# DI.net
KiCad netlist of a schematic drawn in Altium Designer
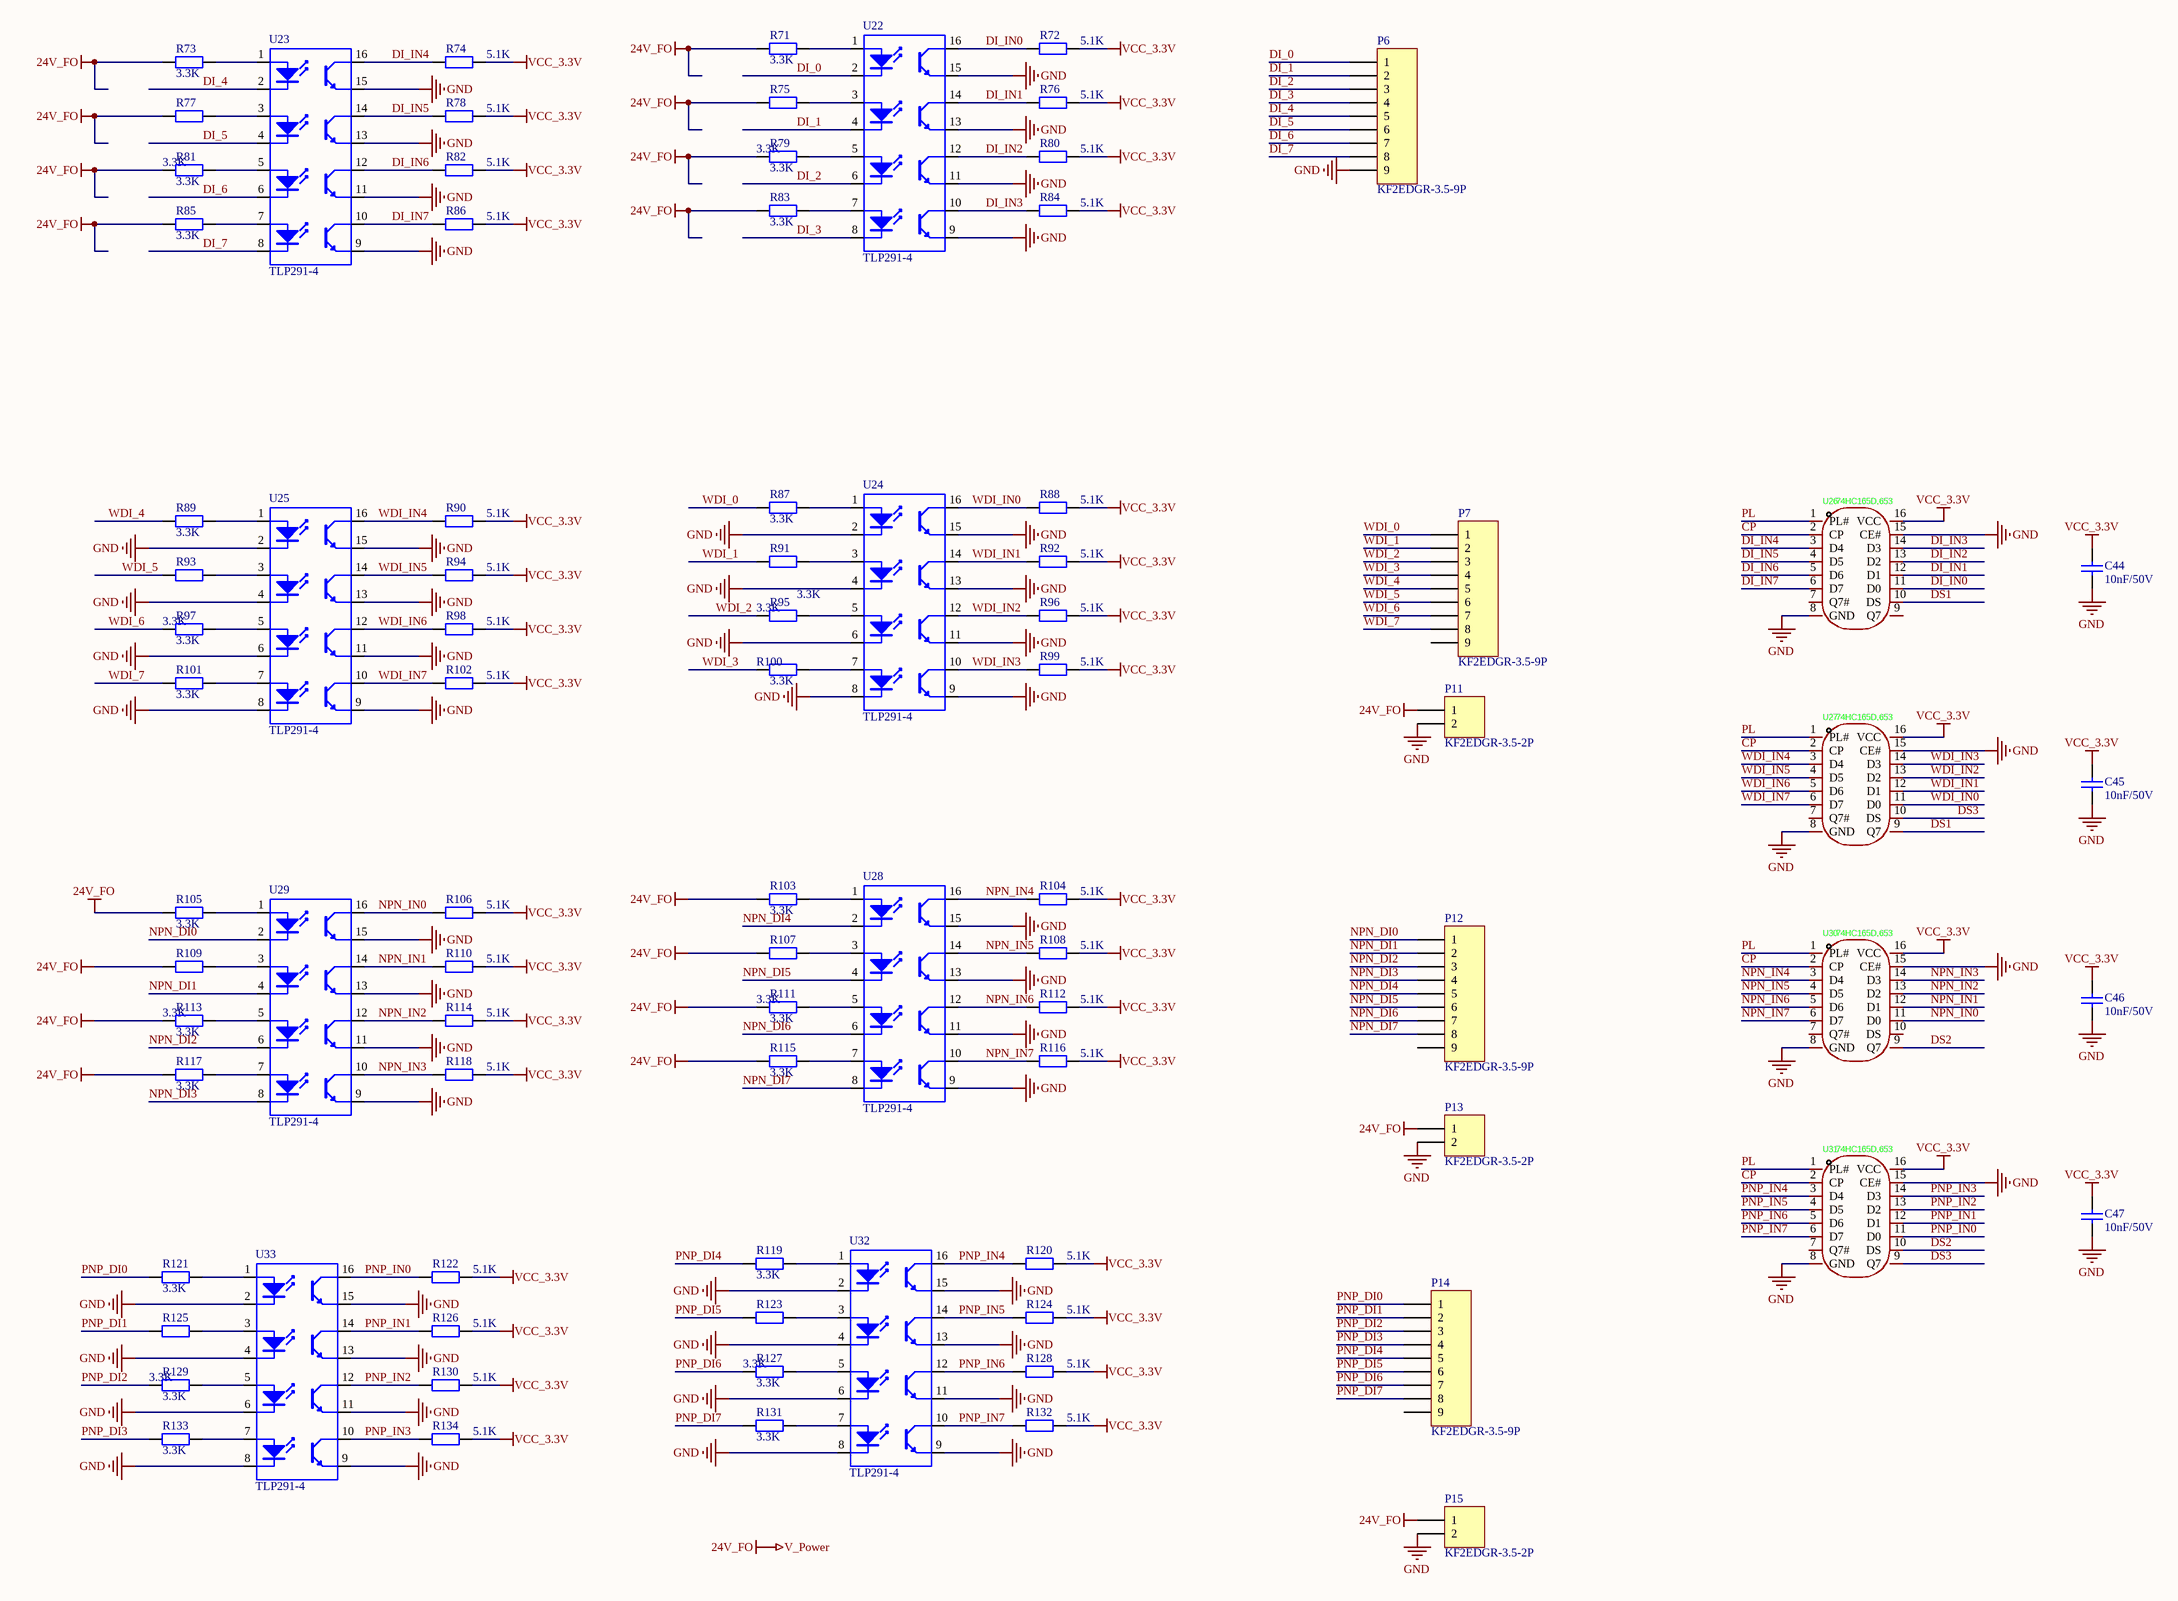
[diagram p0: DI.SchDoc]

(export (version "E")
  (design (tool "Eeschema 10.0.6"))
  (components
    (comp (ref "C44")
      (value "10nF/50V")
      (footprint "0603C")
      (description "Capacitor")
      (libsource (lib "Miscellaneous Devices") (part "Cap"))
    )
    (comp (ref "C45")
      (value "10nF/50V")
      (footprint "0603C")
      (description "Capacitor")
      (libsource (lib "Miscellaneous Devices") (part "Cap"))
    )
    (comp (ref "C46")
      (value "10nF/50V")
      (footprint "0603C")
      (description "Capacitor")
      (libsource (lib "Miscellaneous Devices") (part "Cap"))
    )
    (comp (ref "C47")
      (value "10nF/50V")
      (footprint "0603C")
      (description "Capacitor")
      (libsource (lib "Miscellaneous Devices") (part "Cap"))
    )
    (comp (ref "P6")
      (value "KF2EDGR-3.5-9P")
      (footprint "CONN-TH_9P-P3.50_KF2EDGR-3.5-9P:CONN-TH_9P-P3.50_KF2EDGR-3.5-9P")
      (description "Header, 9-Pin")
      (libsource (lib "Miscellaneous Connectors") (part "Header 9"))
    )
    (comp (ref "P7")
      (value "KF2EDGR-3.5-9P")
      (footprint "CONN-TH_9P-P3.50_KF2EDGR-3.5-9P:CONN-TH_9P-P3.50_KF2EDGR-3.5-9P")
      (description "Header, 9-Pin")
      (libsource (lib "Miscellaneous Connectors") (part "Header 9"))
    )
    (comp (ref "P11")
      (value "KF2EDGR-3.5-2P")
      (footprint "CONN-TH_P3.50_KF2EDGR-3.5-2P:CONN-TH_P3.50_KF2EDGR-3.5-2P")
      (description "Header, 2-Pin")
      (libsource (lib "Miscellaneous Connectors") (part "Header 2"))
    )
    (comp (ref "P12")
      (value "KF2EDGR-3.5-9P")
      (footprint "CONN-TH_9P-P3.50_KF2EDGR-3.5-9P:CONN-TH_9P-P3.50_KF2EDGR-3.5-9P")
      (description "Header, 9-Pin")
      (libsource (lib "Miscellaneous Connectors") (part "Header 9"))
    )
    (comp (ref "P13")
      (value "KF2EDGR-3.5-2P")
      (footprint "CONN-TH_P3.50_KF2EDGR-3.5-2P:CONN-TH_P3.50_KF2EDGR-3.5-2P")
      (description "Header, 2-Pin")
      (libsource (lib "Miscellaneous Connectors") (part "Header 2"))
    )
    (comp (ref "P14")
      (value "KF2EDGR-3.5-9P")
      (footprint "CONN-TH_9P-P3.50_KF2EDGR-3.5-9P:CONN-TH_9P-P3.50_KF2EDGR-3.5-9P")
      (description "Header, 9-Pin")
      (libsource (lib "Miscellaneous Connectors") (part "Header 9"))
    )
    (comp (ref "P15")
      (value "KF2EDGR-3.5-2P")
      (footprint "CONN-TH_P3.50_KF2EDGR-3.5-2P:CONN-TH_P3.50_KF2EDGR-3.5-2P")
      (description "Header, 2-Pin")
      (libsource (lib "Miscellaneous Connectors") (part "Header 2"))
    )
    (comp (ref "R71") (value "3.3K") (footprint "0603R") (libsource (lib "MQlibrary") (part "Res0805M")))
    (comp (ref "R72") (value "5.1K") (footprint "0603R") (libsource (lib "MQlibrary") (part "Res0805M")))
    (comp (ref "R73") (value "3.3K") (footprint "0603R") (libsource (lib "MQlibrary") (part "Res0805M")))
    (comp (ref "R74") (value "5.1K") (footprint "0603R") (libsource (lib "MQlibrary") (part "Res0805M")))
    (comp (ref "R75") (value "3.3K") (footprint "0603R") (libsource (lib "MQlibrary") (part "Res0805M")))
    (comp (ref "R76") (value "5.1K") (footprint "0603R") (libsource (lib "MQlibrary") (part "Res0805M")))
    (comp (ref "R77") (value "3.3K") (footprint "0603R") (libsource (lib "MQlibrary") (part "Res0805M")))
    (comp (ref "R78") (value "5.1K") (footprint "0603R") (libsource (lib "MQlibrary") (part "Res0805M")))
    (comp (ref "R79") (value "3.3K") (footprint "0603R") (libsource (lib "MQlibrary") (part "Res0805M")))
    (comp (ref "R80") (value "5.1K") (footprint "0603R") (libsource (lib "MQlibrary") (part "Res0805M")))
    (comp (ref "R81") (value "3.3K") (footprint "0603R") (libsource (lib "MQlibrary") (part "Res0805M")))
    (comp (ref "R82") (value "5.1K") (footprint "0603R") (libsource (lib "MQlibrary") (part "Res0805M")))
    (comp (ref "R83") (value "3.3K") (footprint "0603R") (libsource (lib "MQlibrary") (part "Res0805M")))
    (comp (ref "R84") (value "5.1K") (footprint "0603R") (libsource (lib "MQlibrary") (part "Res0805M")))
    (comp (ref "R85") (value "3.3K") (footprint "0603R") (libsource (lib "MQlibrary") (part "Res0805M")))
    (comp (ref "R86") (value "5.1K") (footprint "0603R") (libsource (lib "MQlibrary") (part "Res0805M")))
    (comp (ref "R87") (value "3.3K") (footprint "0603R") (libsource (lib "MQlibrary") (part "Res0805M")))
    (comp (ref "R88") (value "5.1K") (footprint "0603R") (libsource (lib "MQlibrary") (part "Res0805M")))
    (comp (ref "R89") (value "3.3K") (footprint "0603R") (libsource (lib "MQlibrary") (part "Res0805M")))
    (comp (ref "R90") (value "5.1K") (footprint "0603R") (libsource (lib "MQlibrary") (part "Res0805M")))
    (comp (ref "R91") (value "3.3K") (footprint "0603R") (libsource (lib "MQlibrary") (part "Res0805M")))
    (comp (ref "R92") (value "5.1K") (footprint "0603R") (libsource (lib "MQlibrary") (part "Res0805M")))
    (comp (ref "R93") (value "3.3K") (footprint "0603R") (libsource (lib "MQlibrary") (part "Res0805M")))
    (comp (ref "R94") (value "5.1K") (footprint "0603R") (libsource (lib "MQlibrary") (part "Res0805M")))
    (comp (ref "R95") (value "3.3K") (footprint "0603R") (libsource (lib "MQlibrary") (part "Res0805M")))
    (comp (ref "R96") (value "5.1K") (footprint "0603R") (libsource (lib "MQlibrary") (part "Res0805M")))
    (comp (ref "R97") (value "3.3K") (footprint "0603R") (libsource (lib "MQlibrary") (part "Res0805M")))
    (comp (ref "R98") (value "5.1K") (footprint "0603R") (libsource (lib "MQlibrary") (part "Res0805M")))
    (comp (ref "R99") (value "5.1K") (footprint "0603R") (libsource (lib "MQlibrary") (part "Res0805M")))
    (comp (ref "R100") (value "3.3K") (footprint "0603R") (libsource (lib "MQlibrary") (part "Res0805M")))
    (comp (ref "R101") (value "3.3K") (footprint "0603R") (libsource (lib "MQlibrary") (part "Res0805M")))
    (comp (ref "R102") (value "5.1K") (footprint "0603R") (libsource (lib "MQlibrary") (part "Res0805M")))
    (comp (ref "R103") (value "3.3K") (footprint "0603R") (libsource (lib "MQlibrary") (part "Res0805M")))
    (comp (ref "R104") (value "5.1K") (footprint "0603R") (libsource (lib "MQlibrary") (part "Res0805M")))
    (comp (ref "R105") (value "3.3K") (footprint "0603R") (libsource (lib "MQlibrary") (part "Res0805M")))
    (comp (ref "R106") (value "5.1K") (footprint "0603R") (libsource (lib "MQlibrary") (part "Res0805M")))
    (comp (ref "R107") (value "3.3K") (footprint "0603R") (libsource (lib "MQlibrary") (part "Res0805M")))
    (comp (ref "R108") (value "5.1K") (footprint "0603R") (libsource (lib "MQlibrary") (part "Res0805M")))
    (comp (ref "R109") (value "3.3K") (footprint "0603R") (libsource (lib "MQlibrary") (part "Res0805M")))
    (comp (ref "R110") (value "5.1K") (footprint "0603R") (libsource (lib "MQlibrary") (part "Res0805M")))
    (comp (ref "R111") (value "3.3K") (footprint "0603R") (libsource (lib "MQlibrary") (part "Res0805M")))
    (comp (ref "R112") (value "5.1K") (footprint "0603R") (libsource (lib "MQlibrary") (part "Res0805M")))
    (comp (ref "R113") (value "3.3K") (footprint "0603R") (libsource (lib "MQlibrary") (part "Res0805M")))
    (comp (ref "R114") (value "5.1K") (footprint "0603R") (libsource (lib "MQlibrary") (part "Res0805M")))
    (comp (ref "R115") (value "3.3K") (footprint "0603R") (libsource (lib "MQlibrary") (part "Res0805M")))
    (comp (ref "R116") (value "5.1K") (footprint "0603R") (libsource (lib "MQlibrary") (part "Res0805M")))
    (comp (ref "R117") (value "3.3K") (footprint "0603R") (libsource (lib "MQlibrary") (part "Res0805M")))
    (comp (ref "R118") (value "5.1K") (footprint "0603R") (libsource (lib "MQlibrary") (part "Res0805M")))
    (comp (ref "R119") (value "3.3K") (footprint "0603R") (libsource (lib "MQlibrary") (part "Res0805M")))
    (comp (ref "R120") (value "5.1K") (footprint "0603R") (libsource (lib "MQlibrary") (part "Res0805M")))
    (comp (ref "R121") (value "3.3K") (footprint "0603R") (libsource (lib "MQlibrary") (part "Res0805M")))
    (comp (ref "R122") (value "5.1K") (footprint "0603R") (libsource (lib "MQlibrary") (part "Res0805M")))
    (comp (ref "R123") (value "3.3K") (footprint "0603R") (libsource (lib "MQlibrary") (part "Res0805M")))
    (comp (ref "R124") (value "5.1K") (footprint "0603R") (libsource (lib "MQlibrary") (part "Res0805M")))
    (comp (ref "R125") (value "3.3K") (footprint "0603R") (libsource (lib "MQlibrary") (part "Res0805M")))
    (comp (ref "R126") (value "5.1K") (footprint "0603R") (libsource (lib "MQlibrary") (part "Res0805M")))
    (comp (ref "R127") (value "3.3K") (footprint "0603R") (libsource (lib "MQlibrary") (part "Res0805M")))
    (comp (ref "R128") (value "5.1K") (footprint "0603R") (libsource (lib "MQlibrary") (part "Res0805M")))
    (comp (ref "R129") (value "3.3K") (footprint "0603R") (libsource (lib "MQlibrary") (part "Res0805M")))
    (comp (ref "R130") (value "5.1K") (footprint "0603R") (libsource (lib "MQlibrary") (part "Res0805M")))
    (comp (ref "R131") (value "3.3K") (footprint "0603R") (libsource (lib "MQlibrary") (part "Res0805M")))
    (comp (ref "R132") (value "5.1K") (footprint "0603R") (libsource (lib "MQlibrary") (part "Res0805M")))
    (comp (ref "R133") (value "3.3K") (footprint "0603R") (libsource (lib "MQlibrary") (part "Res0805M")))
    (comp (ref "R134") (value "5.1K") (footprint "0603R") (libsource (lib "MQlibrary") (part "Res0805M")))
    (comp (ref "U22")
      (value "TLP291-4")
      (footprint "controller_V1.3.1:SOP16-T")
      (libsource (lib "DI16") (part "TLP281-4"))
    )
    (comp (ref "U23")
      (value "TLP291-4")
      (footprint "controller_V1.3.1:SOP16-T")
      (libsource (lib "DI16") (part "TLP281-4"))
    )
    (comp (ref "U24")
      (value "TLP291-4")
      (footprint "controller_V1.3.1:SOP16-T")
      (libsource (lib "DI16") (part "TLP281-4"))
    )
    (comp (ref "U25")
      (value "TLP291-4")
      (footprint "controller_V1.3.1:SOP16-T")
      (libsource (lib "DI16") (part "TLP281-4"))
    )
    (comp (ref "U26")
      (value "74HC165D,653")
      (footprint "Pcblib_20110825:SOP-16_L10.0-W3.9-P1.27-LS6.0-BL")
      (libsource (lib "altium-import") (part "root_0_74HC165D,653_"))
    )
    (comp (ref "U27")
      (value "74HC165D,653")
      (footprint "Pcblib_20110825:SOP-16_L10.0-W3.9-P1.27-LS6.0-BL")
      (libsource (lib "altium-import") (part "root_0_74HC165D,653_"))
    )
    (comp (ref "U28")
      (value "TLP291-4")
      (footprint "controller_V1.3.1:SOP16-T")
      (libsource (lib "DI16") (part "TLP281-4"))
    )
    (comp (ref "U29")
      (value "TLP291-4")
      (footprint "controller_V1.3.1:SOP16-T")
      (libsource (lib "DI16") (part "TLP281-4"))
    )
    (comp (ref "U30")
      (value "74HC165D,653")
      (footprint "SOP-16_L10.0-W3.9-P1.27-LS6.0-BL")
      (libsource (lib "altium-import") (part "root_0_74HC165D,653_"))
    )
    (comp (ref "U31")
      (value "74HC165D,653")
      (footprint "SOP-16_L10.0-W3.9-P1.27-LS6.0-BL")
      (libsource (lib "altium-import") (part "root_0_74HC165D,653_"))
    )
    (comp (ref "U32")
      (value "TLP291-4")
      (footprint "controller_V1.3.1:SOP16-T")
      (libsource (lib "DI16") (part "TLP281-4"))
    )
    (comp (ref "U33")
      (value "TLP291-4")
      (footprint "controller_V1.3.1:SOP16-T")
      (libsource (lib "DI16") (part "TLP281-4"))
    )
  )
  (nets
    (net (code "1") (name "/CP") (class "Default")
      (node (ref "U26") (pin "2") (pinfunction "CP_2") (pintype "passive"))
      (node (ref "U27") (pin "2") (pinfunction "CP_2") (pintype "passive"))
      (node (ref "U30") (pin "2") (pinfunction "CP_2") (pintype "passive"))
      (node (ref "U31") (pin "2") (pinfunction "CP_2") (pintype "passive"))
    )
    (net (code "2") (name "/DI_0") (class "Default")
      (node (ref "P6") (pin "1") (pinfunction "1_1") (pintype "passive"))
      (node (ref "U22") (pin "2") (pinfunction "K_2") (pintype "passive"))
    )
    (net (code "3") (name "/DI_1") (class "Default")
      (node (ref "P6") (pin "2") (pinfunction "2_2") (pintype "passive"))
      (node (ref "U22") (pin "4") (pinfunction "K_4") (pintype "passive"))
    )
    (net (code "4") (name "/DI_2") (class "Default")
      (node (ref "P6") (pin "3") (pinfunction "3_3") (pintype "passive"))
      (node (ref "U22") (pin "6") (pinfunction "K_6") (pintype "passive"))
    )
    (net (code "5") (name "/DI_3") (class "Default")
      (node (ref "P6") (pin "4") (pinfunction "4_4") (pintype "passive"))
      (node (ref "U22") (pin "8") (pinfunction "K_8") (pintype "passive"))
    )
    (net (code "6") (name "/DI_4") (class "Default")
      (node (ref "P6") (pin "5") (pinfunction "5_5") (pintype "passive"))
      (node (ref "U23") (pin "2") (pinfunction "K_2") (pintype "passive"))
    )
    (net (code "7") (name "/DI_5") (class "Default")
      (node (ref "P6") (pin "6") (pinfunction "6_6") (pintype "passive"))
      (node (ref "U23") (pin "4") (pinfunction "K_4") (pintype "passive"))
    )
    (net (code "8") (name "/DI_6") (class "Default")
      (node (ref "P6") (pin "7") (pinfunction "7_7") (pintype "passive"))
      (node (ref "U23") (pin "6") (pinfunction "K_6") (pintype "passive"))
    )
    (net (code "9") (name "/DI_7") (class "Default")
      (node (ref "P6") (pin "8") (pinfunction "8_8") (pintype "passive"))
      (node (ref "U23") (pin "8") (pinfunction "K_8") (pintype "passive"))
    )
    (net (code "10") (name "/DI_IN0") (class "Default")
      (node (ref "R72") (pin "2") (pinfunction "2_2") (pintype "passive"))
      (node (ref "U22") (pin "16") (pinfunction "C_16") (pintype "passive"))
      (node (ref "U26") (pin "11") (pinfunction "D0_11") (pintype "passive"))
    )
    (net (code "11") (name "/DI_IN1") (class "Default")
      (node (ref "R76") (pin "2") (pinfunction "2_2") (pintype "passive"))
      (node (ref "U22") (pin "14") (pinfunction "C_14") (pintype "passive"))
      (node (ref "U26") (pin "12") (pinfunction "D1_12") (pintype "passive"))
    )
    (net (code "12") (name "/DI_IN2") (class "Default")
      (node (ref "R80") (pin "2") (pinfunction "2_2") (pintype "passive"))
      (node (ref "U22") (pin "12") (pinfunction "C_12") (pintype "passive"))
      (node (ref "U26") (pin "13") (pinfunction "D2_13") (pintype "passive"))
    )
    (net (code "13") (name "/DI_IN3") (class "Default")
      (node (ref "R84") (pin "2") (pinfunction "2_2") (pintype "passive"))
      (node (ref "U22") (pin "10") (pinfunction "C_10") (pintype "passive"))
      (node (ref "U26") (pin "14") (pinfunction "D3_14") (pintype "passive"))
    )
    (net (code "14") (name "/DI_IN4") (class "Default")
      (node (ref "R74") (pin "2") (pinfunction "2_2") (pintype "passive"))
      (node (ref "U23") (pin "16") (pinfunction "C_16") (pintype "passive"))
      (node (ref "U26") (pin "3") (pinfunction "D4_3") (pintype "passive"))
    )
    (net (code "15") (name "/DI_IN5") (class "Default")
      (node (ref "R78") (pin "2") (pinfunction "2_2") (pintype "passive"))
      (node (ref "U23") (pin "14") (pinfunction "C_14") (pintype "passive"))
      (node (ref "U26") (pin "4") (pinfunction "D5_4") (pintype "passive"))
    )
    (net (code "16") (name "/DI_IN6") (class "Default")
      (node (ref "R82") (pin "2") (pinfunction "2_2") (pintype "passive"))
      (node (ref "U23") (pin "12") (pinfunction "C_12") (pintype "passive"))
      (node (ref "U26") (pin "5") (pinfunction "D6_5") (pintype "passive"))
    )
    (net (code "17") (name "/DI_IN7") (class "Default")
      (node (ref "R86") (pin "2") (pinfunction "2_2") (pintype "passive"))
      (node (ref "U23") (pin "10") (pinfunction "C_10") (pintype "passive"))
      (node (ref "U26") (pin "6") (pinfunction "D7_6") (pintype "passive"))
    )
    (net (code "18") (name "/DS1") (class "Default")
      (node (ref "U26") (pin "10") (pinfunction "DS_10") (pintype "passive"))
      (node (ref "U27") (pin "9") (pinfunction "Q7_9") (pintype "passive"))
    )
    (net (code "19") (name "/DS2") (class "Default")
      (node (ref "U30") (pin "9") (pinfunction "Q7_9") (pintype "passive"))
      (node (ref "U31") (pin "10") (pinfunction "DS_10") (pintype "passive"))
    )
    (net (code "20") (name "/DS3") (class "Default")
      (node (ref "U27") (pin "10") (pinfunction "DS_10") (pintype "passive"))
      (node (ref "U31") (pin "9") (pinfunction "Q7_9") (pintype "passive"))
    )
    (net (code "21") (name "/NPN_DI0") (class "Default")
      (node (ref "P12") (pin "1") (pinfunction "1_1") (pintype "passive"))
      (node (ref "U29") (pin "2") (pinfunction "K_2") (pintype "passive"))
    )
    (net (code "22") (name "/NPN_DI1") (class "Default")
      (node (ref "P12") (pin "2") (pinfunction "2_2") (pintype "passive"))
      (node (ref "U29") (pin "4") (pinfunction "K_4") (pintype "passive"))
    )
    (net (code "23") (name "/NPN_DI2") (class "Default")
      (node (ref "P12") (pin "3") (pinfunction "3_3") (pintype "passive"))
      (node (ref "U29") (pin "6") (pinfunction "K_6") (pintype "passive"))
    )
    (net (code "24") (name "/NPN_DI3") (class "Default")
      (node (ref "P12") (pin "4") (pinfunction "4_4") (pintype "passive"))
      (node (ref "U29") (pin "8") (pinfunction "K_8") (pintype "passive"))
    )
    (net (code "25") (name "/NPN_DI4") (class "Default")
      (node (ref "P12") (pin "5") (pinfunction "5_5") (pintype "passive"))
      (node (ref "U28") (pin "2") (pinfunction "K_2") (pintype "passive"))
    )
    (net (code "26") (name "/NPN_DI5") (class "Default")
      (node (ref "P12") (pin "6") (pinfunction "6_6") (pintype "passive"))
      (node (ref "U28") (pin "4") (pinfunction "K_4") (pintype "passive"))
    )
    (net (code "27") (name "/NPN_DI6") (class "Default")
      (node (ref "P12") (pin "7") (pinfunction "7_7") (pintype "passive"))
      (node (ref "U28") (pin "6") (pinfunction "K_6") (pintype "passive"))
    )
    (net (code "28") (name "/NPN_DI7") (class "Default")
      (node (ref "P12") (pin "8") (pinfunction "8_8") (pintype "passive"))
      (node (ref "U28") (pin "8") (pinfunction "K_8") (pintype "passive"))
    )
    (net (code "29") (name "/NPN_IN0") (class "Default")
      (node (ref "R106") (pin "2") (pinfunction "2_2") (pintype "passive"))
      (node (ref "U29") (pin "16") (pinfunction "C_16") (pintype "passive"))
      (node (ref "U30") (pin "11") (pinfunction "D0_11") (pintype "passive"))
    )
    (net (code "30") (name "/NPN_IN1") (class "Default")
      (node (ref "R110") (pin "2") (pinfunction "2_2") (pintype "passive"))
      (node (ref "U29") (pin "14") (pinfunction "C_14") (pintype "passive"))
      (node (ref "U30") (pin "12") (pinfunction "D1_12") (pintype "passive"))
    )
    (net (code "31") (name "/NPN_IN2") (class "Default")
      (node (ref "R114") (pin "2") (pinfunction "2_2") (pintype "passive"))
      (node (ref "U29") (pin "12") (pinfunction "C_12") (pintype "passive"))
      (node (ref "U30") (pin "13") (pinfunction "D2_13") (pintype "passive"))
    )
    (net (code "32") (name "/NPN_IN3") (class "Default")
      (node (ref "R118") (pin "2") (pinfunction "2_2") (pintype "passive"))
      (node (ref "U29") (pin "10") (pinfunction "C_10") (pintype "passive"))
      (node (ref "U30") (pin "14") (pinfunction "D3_14") (pintype "passive"))
    )
    (net (code "33") (name "/NPN_IN4") (class "Default")
      (node (ref "R104") (pin "2") (pinfunction "2_2") (pintype "passive"))
      (node (ref "U28") (pin "16") (pinfunction "C_16") (pintype "passive"))
      (node (ref "U30") (pin "3") (pinfunction "D4_3") (pintype "passive"))
    )
    (net (code "34") (name "/NPN_IN5") (class "Default")
      (node (ref "R108") (pin "2") (pinfunction "2_2") (pintype "passive"))
      (node (ref "U28") (pin "14") (pinfunction "C_14") (pintype "passive"))
      (node (ref "U30") (pin "4") (pinfunction "D5_4") (pintype "passive"))
    )
    (net (code "35") (name "/NPN_IN6") (class "Default")
      (node (ref "R112") (pin "2") (pinfunction "2_2") (pintype "passive"))
      (node (ref "U28") (pin "12") (pinfunction "C_12") (pintype "passive"))
      (node (ref "U30") (pin "5") (pinfunction "D6_5") (pintype "passive"))
    )
    (net (code "36") (name "/NPN_IN7") (class "Default")
      (node (ref "R116") (pin "2") (pinfunction "2_2") (pintype "passive"))
      (node (ref "U28") (pin "10") (pinfunction "C_10") (pintype "passive"))
      (node (ref "U30") (pin "6") (pinfunction "D7_6") (pintype "passive"))
    )
    (net (code "37") (name "/PL") (class "Default")
      (node (ref "U26") (pin "1") (pinfunction "PL#_1") (pintype "passive"))
      (node (ref "U27") (pin "1") (pinfunction "PL#_1") (pintype "passive"))
      (node (ref "U30") (pin "1") (pinfunction "PL#_1") (pintype "passive"))
      (node (ref "U31") (pin "1") (pinfunction "PL#_1") (pintype "passive"))
    )
    (net (code "38") (name "/PNP_DI0") (class "Default")
      (node (ref "P14") (pin "1") (pinfunction "1_1") (pintype "passive"))
      (node (ref "R121") (pin "2") (pinfunction "2_2") (pintype "passive"))
    )
    (net (code "39") (name "/PNP_DI1") (class "Default")
      (node (ref "P14") (pin "2") (pinfunction "2_2") (pintype "passive"))
      (node (ref "R125") (pin "2") (pinfunction "2_2") (pintype "passive"))
    )
    (net (code "40") (name "/PNP_DI2") (class "Default")
      (node (ref "P14") (pin "3") (pinfunction "3_3") (pintype "passive"))
      (node (ref "R129") (pin "2") (pinfunction "2_2") (pintype "passive"))
    )
    (net (code "41") (name "/PNP_DI3") (class "Default")
      (node (ref "P14") (pin "4") (pinfunction "4_4") (pintype "passive"))
      (node (ref "R133") (pin "2") (pinfunction "2_2") (pintype "passive"))
    )
    (net (code "42") (name "/PNP_DI4") (class "Default")
      (node (ref "P14") (pin "5") (pinfunction "5_5") (pintype "passive"))
      (node (ref "R119") (pin "2") (pinfunction "2_2") (pintype "passive"))
    )
    (net (code "43") (name "/PNP_DI5") (class "Default")
      (node (ref "P14") (pin "6") (pinfunction "6_6") (pintype "passive"))
      (node (ref "R123") (pin "2") (pinfunction "2_2") (pintype "passive"))
    )
    (net (code "44") (name "/PNP_DI6") (class "Default")
      (node (ref "P14") (pin "7") (pinfunction "7_7") (pintype "passive"))
      (node (ref "R127") (pin "2") (pinfunction "2_2") (pintype "passive"))
    )
    (net (code "45") (name "/PNP_DI7") (class "Default")
      (node (ref "P14") (pin "8") (pinfunction "8_8") (pintype "passive"))
      (node (ref "R131") (pin "2") (pinfunction "2_2") (pintype "passive"))
    )
    (net (code "46") (name "/PNP_IN0") (class "Default")
      (node (ref "R122") (pin "2") (pinfunction "2_2") (pintype "passive"))
      (node (ref "U31") (pin "11") (pinfunction "D0_11") (pintype "passive"))
      (node (ref "U33") (pin "16") (pinfunction "C_16") (pintype "passive"))
    )
    (net (code "47") (name "/PNP_IN1") (class "Default")
      (node (ref "R126") (pin "2") (pinfunction "2_2") (pintype "passive"))
      (node (ref "U31") (pin "12") (pinfunction "D1_12") (pintype "passive"))
      (node (ref "U33") (pin "14") (pinfunction "C_14") (pintype "passive"))
    )
    (net (code "48") (name "/PNP_IN2") (class "Default")
      (node (ref "R130") (pin "2") (pinfunction "2_2") (pintype "passive"))
      (node (ref "U31") (pin "13") (pinfunction "D2_13") (pintype "passive"))
      (node (ref "U33") (pin "12") (pinfunction "C_12") (pintype "passive"))
    )
    (net (code "49") (name "/PNP_IN3") (class "Default")
      (node (ref "R134") (pin "2") (pinfunction "2_2") (pintype "passive"))
      (node (ref "U31") (pin "14") (pinfunction "D3_14") (pintype "passive"))
      (node (ref "U33") (pin "10") (pinfunction "C_10") (pintype "passive"))
    )
    (net (code "50") (name "/PNP_IN4") (class "Default")
      (node (ref "R120") (pin "2") (pinfunction "2_2") (pintype "passive"))
      (node (ref "U31") (pin "3") (pinfunction "D4_3") (pintype "passive"))
      (node (ref "U32") (pin "16") (pinfunction "C_16") (pintype "passive"))
    )
    (net (code "51") (name "/PNP_IN5") (class "Default")
      (node (ref "R124") (pin "2") (pinfunction "2_2") (pintype "passive"))
      (node (ref "U31") (pin "4") (pinfunction "D5_4") (pintype "passive"))
      (node (ref "U32") (pin "14") (pinfunction "C_14") (pintype "passive"))
    )
    (net (code "52") (name "/PNP_IN6") (class "Default")
      (node (ref "R128") (pin "2") (pinfunction "2_2") (pintype "passive"))
      (node (ref "U31") (pin "5") (pinfunction "D6_5") (pintype "passive"))
      (node (ref "U32") (pin "12") (pinfunction "C_12") (pintype "passive"))
    )
    (net (code "53") (name "/PNP_IN7") (class "Default")
      (node (ref "R132") (pin "2") (pinfunction "2_2") (pintype "passive"))
      (node (ref "U31") (pin "6") (pinfunction "D7_6") (pintype "passive"))
      (node (ref "U32") (pin "10") (pinfunction "C_10") (pintype "passive"))
    )
    (net (code "54") (name "/WDI_0") (class "Default")
      (node (ref "P7") (pin "1") (pinfunction "1_1") (pintype "passive"))
      (node (ref "R87") (pin "2") (pinfunction "2_2") (pintype "passive"))
    )
    (net (code "55") (name "/WDI_1") (class "Default")
      (node (ref "P7") (pin "2") (pinfunction "2_2") (pintype "passive"))
      (node (ref "R91") (pin "2") (pinfunction "2_2") (pintype "passive"))
    )
    (net (code "56") (name "/WDI_2") (class "Default")
      (node (ref "P7") (pin "3") (pinfunction "3_3") (pintype "passive"))
      (node (ref "R95") (pin "2") (pinfunction "2_2") (pintype "passive"))
    )
    (net (code "57") (name "/WDI_3") (class "Default")
      (node (ref "P7") (pin "4") (pinfunction "4_4") (pintype "passive"))
      (node (ref "R100") (pin "2") (pinfunction "2_2") (pintype "passive"))
    )
    (net (code "58") (name "/WDI_4") (class "Default")
      (node (ref "P7") (pin "5") (pinfunction "5_5") (pintype "passive"))
      (node (ref "R89") (pin "2") (pinfunction "2_2") (pintype "passive"))
    )
    (net (code "59") (name "/WDI_5") (class "Default")
      (node (ref "P7") (pin "6") (pinfunction "6_6") (pintype "passive"))
      (node (ref "R93") (pin "2") (pinfunction "2_2") (pintype "passive"))
    )
    (net (code "60") (name "/WDI_6") (class "Default")
      (node (ref "P7") (pin "7") (pinfunction "7_7") (pintype "passive"))
      (node (ref "R97") (pin "2") (pinfunction "2_2") (pintype "passive"))
    )
    (net (code "61") (name "/WDI_7") (class "Default")
      (node (ref "P7") (pin "8") (pinfunction "8_8") (pintype "passive"))
      (node (ref "R101") (pin "2") (pinfunction "2_2") (pintype "passive"))
    )
    (net (code "62") (name "/WDI_IN0") (class "Default")
      (node (ref "R88") (pin "2") (pinfunction "2_2") (pintype "passive"))
      (node (ref "U24") (pin "16") (pinfunction "C_16") (pintype "passive"))
      (node (ref "U27") (pin "11") (pinfunction "D0_11") (pintype "passive"))
    )
    (net (code "63") (name "/WDI_IN1") (class "Default")
      (node (ref "R92") (pin "2") (pinfunction "2_2") (pintype "passive"))
      (node (ref "U24") (pin "14") (pinfunction "C_14") (pintype "passive"))
      (node (ref "U27") (pin "12") (pinfunction "D1_12") (pintype "passive"))
    )
    (net (code "64") (name "/WDI_IN2") (class "Default")
      (node (ref "R96") (pin "2") (pinfunction "2_2") (pintype "passive"))
      (node (ref "U24") (pin "12") (pinfunction "C_12") (pintype "passive"))
      (node (ref "U27") (pin "13") (pinfunction "D2_13") (pintype "passive"))
    )
    (net (code "65") (name "/WDI_IN3") (class "Default")
      (node (ref "R99") (pin "2") (pinfunction "2_2") (pintype "passive"))
      (node (ref "U24") (pin "10") (pinfunction "C_10") (pintype "passive"))
      (node (ref "U27") (pin "14") (pinfunction "D3_14") (pintype "passive"))
    )
    (net (code "66") (name "/WDI_IN4") (class "Default")
      (node (ref "R90") (pin "2") (pinfunction "2_2") (pintype "passive"))
      (node (ref "U25") (pin "16") (pinfunction "C_16") (pintype "passive"))
      (node (ref "U27") (pin "3") (pinfunction "D4_3") (pintype "passive"))
    )
    (net (code "67") (name "/WDI_IN5") (class "Default")
      (node (ref "R94") (pin "2") (pinfunction "2_2") (pintype "passive"))
      (node (ref "U25") (pin "14") (pinfunction "C_14") (pintype "passive"))
      (node (ref "U27") (pin "4") (pinfunction "D5_4") (pintype "passive"))
    )
    (net (code "68") (name "/WDI_IN6") (class "Default")
      (node (ref "R98") (pin "2") (pinfunction "2_2") (pintype "passive"))
      (node (ref "U25") (pin "12") (pinfunction "C_12") (pintype "passive"))
      (node (ref "U27") (pin "5") (pinfunction "D6_5") (pintype "passive"))
    )
    (net (code "69") (name "/WDI_IN7") (class "Default")
      (node (ref "R102") (pin "2") (pinfunction "2_2") (pintype "passive"))
      (node (ref "U25") (pin "10") (pinfunction "C_10") (pintype "passive"))
      (node (ref "U27") (pin "6") (pinfunction "D7_6") (pintype "passive"))
    )
    (net (code "70") (name "24V_FO") (class "Default")
      (node (ref "P11") (pin "1") (pinfunction "1_1") (pintype "passive"))
      (node (ref "P13") (pin "1") (pinfunction "1_1") (pintype "passive"))
      (node (ref "P15") (pin "1") (pinfunction "1_1") (pintype "passive"))
      (node (ref "R103") (pin "2") (pinfunction "2_2") (pintype "passive"))
      (node (ref "R105") (pin "2") (pinfunction "2_2") (pintype "passive"))
      (node (ref "R107") (pin "2") (pinfunction "2_2") (pintype "passive"))
      (node (ref "R109") (pin "2") (pinfunction "2_2") (pintype "passive"))
      (node (ref "R111") (pin "2") (pinfunction "2_2") (pintype "passive"))
      (node (ref "R113") (pin "2") (pinfunction "2_2") (pintype "passive"))
      (node (ref "R115") (pin "2") (pinfunction "2_2") (pintype "passive"))
      (node (ref "R117") (pin "2") (pinfunction "2_2") (pintype "passive"))
      (node (ref "R71") (pin "2") (pinfunction "2_2") (pintype "passive"))
      (node (ref "R73") (pin "2") (pinfunction "2_2") (pintype "passive"))
      (node (ref "R75") (pin "2") (pinfunction "2_2") (pintype "passive"))
      (node (ref "R77") (pin "2") (pinfunction "2_2") (pintype "passive"))
      (node (ref "R79") (pin "2") (pinfunction "2_2") (pintype "passive"))
      (node (ref "R81") (pin "2") (pinfunction "2_2") (pintype "passive"))
      (node (ref "R83") (pin "2") (pinfunction "2_2") (pintype "passive"))
      (node (ref "R85") (pin "2") (pinfunction "2_2") (pintype "passive"))
    )
    (net (code "71") (name "GND") (class "Default")
      (node (ref "C44") (pin "1") (pinfunction "1_1") (pintype "passive"))
      (node (ref "C45") (pin "1") (pinfunction "1_1") (pintype "passive"))
      (node (ref "C46") (pin "1") (pinfunction "1_1") (pintype "passive"))
      (node (ref "C47") (pin "1") (pinfunction "1_1") (pintype "passive"))
      (node (ref "P11") (pin "2") (pinfunction "2_2") (pintype "passive"))
      (node (ref "P13") (pin "2") (pinfunction "2_2") (pintype "passive"))
      (node (ref "P15") (pin "2") (pinfunction "2_2") (pintype "passive"))
      (node (ref "P6") (pin "9") (pinfunction "9_9") (pintype "passive"))
      (node (ref "U22") (pin "11") (pinfunction "E_11") (pintype "passive"))
      (node (ref "U22") (pin "13") (pinfunction "E_13") (pintype "passive"))
      (node (ref "U22") (pin "15") (pinfunction "E_15") (pintype "passive"))
      (node (ref "U22") (pin "9") (pinfunction "E_9") (pintype "passive"))
      (node (ref "U23") (pin "11") (pinfunction "E_11") (pintype "passive"))
      (node (ref "U23") (pin "13") (pinfunction "E_13") (pintype "passive"))
      (node (ref "U23") (pin "15") (pinfunction "E_15") (pintype "passive"))
      (node (ref "U23") (pin "9") (pinfunction "E_9") (pintype "passive"))
      (node (ref "U24") (pin "11") (pinfunction "E_11") (pintype "passive"))
      (node (ref "U24") (pin "13") (pinfunction "E_13") (pintype "passive"))
      (node (ref "U24") (pin "15") (pinfunction "E_15") (pintype "passive"))
      (node (ref "U24") (pin "2") (pinfunction "K_2") (pintype "passive"))
      (node (ref "U24") (pin "4") (pinfunction "K_4") (pintype "passive"))
      (node (ref "U24") (pin "6") (pinfunction "K_6") (pintype "passive"))
      (node (ref "U24") (pin "8") (pinfunction "K_8") (pintype "passive"))
      (node (ref "U24") (pin "9") (pinfunction "E_9") (pintype "passive"))
      (node (ref "U25") (pin "11") (pinfunction "E_11") (pintype "passive"))
      (node (ref "U25") (pin "13") (pinfunction "E_13") (pintype "passive"))
      (node (ref "U25") (pin "15") (pinfunction "E_15") (pintype "passive"))
      (node (ref "U25") (pin "2") (pinfunction "K_2") (pintype "passive"))
      (node (ref "U25") (pin "4") (pinfunction "K_4") (pintype "passive"))
      (node (ref "U25") (pin "6") (pinfunction "K_6") (pintype "passive"))
      (node (ref "U25") (pin "8") (pinfunction "K_8") (pintype "passive"))
      (node (ref "U25") (pin "9") (pinfunction "E_9") (pintype "passive"))
      (node (ref "U26") (pin "15") (pinfunction "CE#_15") (pintype "passive"))
      (node (ref "U26") (pin "8") (pinfunction "GND_8") (pintype "passive"))
      (node (ref "U27") (pin "15") (pinfunction "CE#_15") (pintype "passive"))
      (node (ref "U27") (pin "8") (pinfunction "GND_8") (pintype "passive"))
      (node (ref "U28") (pin "11") (pinfunction "E_11") (pintype "passive"))
      (node (ref "U28") (pin "13") (pinfunction "E_13") (pintype "passive"))
      (node (ref "U28") (pin "15") (pinfunction "E_15") (pintype "passive"))
      (node (ref "U28") (pin "9") (pinfunction "E_9") (pintype "passive"))
      (node (ref "U29") (pin "11") (pinfunction "E_11") (pintype "passive"))
      (node (ref "U29") (pin "13") (pinfunction "E_13") (pintype "passive"))
      (node (ref "U29") (pin "15") (pinfunction "E_15") (pintype "passive"))
      (node (ref "U29") (pin "9") (pinfunction "E_9") (pintype "passive"))
      (node (ref "U30") (pin "15") (pinfunction "CE#_15") (pintype "passive"))
      (node (ref "U30") (pin "8") (pinfunction "GND_8") (pintype "passive"))
      (node (ref "U31") (pin "15") (pinfunction "CE#_15") (pintype "passive"))
      (node (ref "U31") (pin "8") (pinfunction "GND_8") (pintype "passive"))
      (node (ref "U32") (pin "11") (pinfunction "E_11") (pintype "passive"))
      (node (ref "U32") (pin "13") (pinfunction "E_13") (pintype "passive"))
      (node (ref "U32") (pin "15") (pinfunction "E_15") (pintype "passive"))
      (node (ref "U32") (pin "2") (pinfunction "K_2") (pintype "passive"))
      (node (ref "U32") (pin "4") (pinfunction "K_4") (pintype "passive"))
      (node (ref "U32") (pin "6") (pinfunction "K_6") (pintype "passive"))
      (node (ref "U32") (pin "8") (pinfunction "K_8") (pintype "passive"))
      (node (ref "U32") (pin "9") (pinfunction "E_9") (pintype "passive"))
      (node (ref "U33") (pin "11") (pinfunction "E_11") (pintype "passive"))
      (node (ref "U33") (pin "13") (pinfunction "E_13") (pintype "passive"))
      (node (ref "U33") (pin "15") (pinfunction "E_15") (pintype "passive"))
      (node (ref "U33") (pin "2") (pinfunction "K_2") (pintype "passive"))
      (node (ref "U33") (pin "4") (pinfunction "K_4") (pintype "passive"))
      (node (ref "U33") (pin "6") (pinfunction "K_6") (pintype "passive"))
      (node (ref "U33") (pin "8") (pinfunction "K_8") (pintype "passive"))
      (node (ref "U33") (pin "9") (pinfunction "E_9") (pintype "passive"))
    )
    (net (code "72") (name "Net-(R71-Pad1)") (class "Default")
      (node (ref "R71") (pin "1") (pinfunction "1_1") (pintype "passive"))
      (node (ref "U22") (pin "1") (pinfunction "A_1") (pintype "passive"))
    )
    (net (code "73") (name "Net-(R73-Pad1)") (class "Default")
      (node (ref "R73") (pin "1") (pinfunction "1_1") (pintype "passive"))
      (node (ref "U23") (pin "1") (pinfunction "A_1") (pintype "passive"))
    )
    (net (code "74") (name "Net-(R75-Pad1)") (class "Default")
      (node (ref "R75") (pin "1") (pinfunction "1_1") (pintype "passive"))
      (node (ref "U22") (pin "3") (pinfunction "A_3") (pintype "passive"))
    )
    (net (code "75") (name "Net-(R77-Pad1)") (class "Default")
      (node (ref "R77") (pin "1") (pinfunction "1_1") (pintype "passive"))
      (node (ref "U23") (pin "3") (pinfunction "A_3") (pintype "passive"))
    )
    (net (code "76") (name "Net-(R79-Pad1)") (class "Default")
      (node (ref "R79") (pin "1") (pinfunction "1_1") (pintype "passive"))
      (node (ref "U22") (pin "5") (pinfunction "A_5") (pintype "passive"))
    )
    (net (code "77") (name "Net-(R81-Pad1)") (class "Default")
      (node (ref "R81") (pin "1") (pinfunction "1_1") (pintype "passive"))
      (node (ref "U23") (pin "5") (pinfunction "A_5") (pintype "passive"))
    )
    (net (code "78") (name "Net-(R83-Pad1)") (class "Default")
      (node (ref "R83") (pin "1") (pinfunction "1_1") (pintype "passive"))
      (node (ref "U22") (pin "7") (pinfunction "A_7") (pintype "passive"))
    )
    (net (code "79") (name "Net-(R85-Pad1)") (class "Default")
      (node (ref "R85") (pin "1") (pinfunction "1_1") (pintype "passive"))
      (node (ref "U23") (pin "7") (pinfunction "A_7") (pintype "passive"))
    )
    (net (code "80") (name "Net-(R87-Pad1)") (class "Default")
      (node (ref "R87") (pin "1") (pinfunction "1_1") (pintype "passive"))
      (node (ref "U24") (pin "1") (pinfunction "A_1") (pintype "passive"))
    )
    (net (code "81") (name "Net-(R89-Pad1)") (class "Default")
      (node (ref "R89") (pin "1") (pinfunction "1_1") (pintype "passive"))
      (node (ref "U25") (pin "1") (pinfunction "A_1") (pintype "passive"))
    )
    (net (code "82") (name "Net-(R91-Pad1)") (class "Default")
      (node (ref "R91") (pin "1") (pinfunction "1_1") (pintype "passive"))
      (node (ref "U24") (pin "3") (pinfunction "A_3") (pintype "passive"))
    )
    (net (code "83") (name "Net-(R93-Pad1)") (class "Default")
      (node (ref "R93") (pin "1") (pinfunction "1_1") (pintype "passive"))
      (node (ref "U25") (pin "3") (pinfunction "A_3") (pintype "passive"))
    )
    (net (code "84") (name "Net-(R95-Pad1)") (class "Default")
      (node (ref "R95") (pin "1") (pinfunction "1_1") (pintype "passive"))
      (node (ref "U24") (pin "5") (pinfunction "A_5") (pintype "passive"))
    )
    (net (code "85") (name "Net-(R97-Pad1)") (class "Default")
      (node (ref "R97") (pin "1") (pinfunction "1_1") (pintype "passive"))
      (node (ref "U25") (pin "5") (pinfunction "A_5") (pintype "passive"))
    )
    (net (code "86") (name "Net-(R100-Pad1)") (class "Default")
      (node (ref "R100") (pin "1") (pinfunction "1_1") (pintype "passive"))
      (node (ref "U24") (pin "7") (pinfunction "A_7") (pintype "passive"))
    )
    (net (code "87") (name "Net-(R101-Pad1)") (class "Default")
      (node (ref "R101") (pin "1") (pinfunction "1_1") (pintype "passive"))
      (node (ref "U25") (pin "7") (pinfunction "A_7") (pintype "passive"))
    )
    (net (code "88") (name "Net-(R103-Pad1)") (class "Default")
      (node (ref "R103") (pin "1") (pinfunction "1_1") (pintype "passive"))
      (node (ref "U28") (pin "1") (pinfunction "A_1") (pintype "passive"))
    )
    (net (code "89") (name "Net-(R105-Pad1)") (class "Default")
      (node (ref "R105") (pin "1") (pinfunction "1_1") (pintype "passive"))
      (node (ref "U29") (pin "1") (pinfunction "A_1") (pintype "passive"))
    )
    (net (code "90") (name "Net-(R107-Pad1)") (class "Default")
      (node (ref "R107") (pin "1") (pinfunction "1_1") (pintype "passive"))
      (node (ref "U28") (pin "3") (pinfunction "A_3") (pintype "passive"))
    )
    (net (code "91") (name "Net-(R109-Pad1)") (class "Default")
      (node (ref "R109") (pin "1") (pinfunction "1_1") (pintype "passive"))
      (node (ref "U29") (pin "3") (pinfunction "A_3") (pintype "passive"))
    )
    (net (code "92") (name "Net-(R111-Pad1)") (class "Default")
      (node (ref "R111") (pin "1") (pinfunction "1_1") (pintype "passive"))
      (node (ref "U28") (pin "5") (pinfunction "A_5") (pintype "passive"))
    )
    (net (code "93") (name "Net-(R113-Pad1)") (class "Default")
      (node (ref "R113") (pin "1") (pinfunction "1_1") (pintype "passive"))
      (node (ref "U29") (pin "5") (pinfunction "A_5") (pintype "passive"))
    )
    (net (code "94") (name "Net-(R115-Pad1)") (class "Default")
      (node (ref "R115") (pin "1") (pinfunction "1_1") (pintype "passive"))
      (node (ref "U28") (pin "7") (pinfunction "A_7") (pintype "passive"))
    )
    (net (code "95") (name "Net-(R117-Pad1)") (class "Default")
      (node (ref "R117") (pin "1") (pinfunction "1_1") (pintype "passive"))
      (node (ref "U29") (pin "7") (pinfunction "A_7") (pintype "passive"))
    )
    (net (code "96") (name "Net-(R119-Pad1)") (class "Default")
      (node (ref "R119") (pin "1") (pinfunction "1_1") (pintype "passive"))
      (node (ref "U32") (pin "1") (pinfunction "A_1") (pintype "passive"))
    )
    (net (code "97") (name "Net-(R121-Pad1)") (class "Default")
      (node (ref "R121") (pin "1") (pinfunction "1_1") (pintype "passive"))
      (node (ref "U33") (pin "1") (pinfunction "A_1") (pintype "passive"))
    )
    (net (code "98") (name "Net-(R123-Pad1)") (class "Default")
      (node (ref "R123") (pin "1") (pinfunction "1_1") (pintype "passive"))
      (node (ref "U32") (pin "3") (pinfunction "A_3") (pintype "passive"))
    )
    (net (code "99") (name "Net-(R125-Pad1)") (class "Default")
      (node (ref "R125") (pin "1") (pinfunction "1_1") (pintype "passive"))
      (node (ref "U33") (pin "3") (pinfunction "A_3") (pintype "passive"))
    )
    (net (code "100") (name "Net-(R127-Pad1)") (class "Default")
      (node (ref "R127") (pin "1") (pinfunction "1_1") (pintype "passive"))
      (node (ref "U32") (pin "5") (pinfunction "A_5") (pintype "passive"))
    )
    (net (code "101") (name "Net-(R129-Pad1)") (class "Default")
      (node (ref "R129") (pin "1") (pinfunction "1_1") (pintype "passive"))
      (node (ref "U33") (pin "5") (pinfunction "A_5") (pintype "passive"))
    )
    (net (code "102") (name "Net-(R131-Pad1)") (class "Default")
      (node (ref "R131") (pin "1") (pinfunction "1_1") (pintype "passive"))
      (node (ref "U32") (pin "7") (pinfunction "A_7") (pintype "passive"))
    )
    (net (code "103") (name "Net-(R133-Pad1)") (class "Default")
      (node (ref "R133") (pin "1") (pinfunction "1_1") (pintype "passive"))
      (node (ref "U33") (pin "7") (pinfunction "A_7") (pintype "passive"))
    )
    (net (code "104") (name "VCC_3.3V") (class "Default")
      (node (ref "C44") (pin "2") (pinfunction "2_2") (pintype "passive"))
      (node (ref "C45") (pin "2") (pinfunction "2_2") (pintype "passive"))
      (node (ref "C46") (pin "2") (pinfunction "2_2") (pintype "passive"))
      (node (ref "C47") (pin "2") (pinfunction "2_2") (pintype "passive"))
      (node (ref "R102") (pin "1") (pinfunction "1_1") (pintype "passive"))
      (node (ref "R104") (pin "1") (pinfunction "1_1") (pintype "passive"))
      (node (ref "R106") (pin "1") (pinfunction "1_1") (pintype "passive"))
      (node (ref "R108") (pin "1") (pinfunction "1_1") (pintype "passive"))
      (node (ref "R110") (pin "1") (pinfunction "1_1") (pintype "passive"))
      (node (ref "R112") (pin "1") (pinfunction "1_1") (pintype "passive"))
      (node (ref "R114") (pin "1") (pinfunction "1_1") (pintype "passive"))
      (node (ref "R116") (pin "1") (pinfunction "1_1") (pintype "passive"))
      (node (ref "R118") (pin "1") (pinfunction "1_1") (pintype "passive"))
      (node (ref "R120") (pin "1") (pinfunction "1_1") (pintype "passive"))
      (node (ref "R122") (pin "1") (pinfunction "1_1") (pintype "passive"))
      (node (ref "R124") (pin "1") (pinfunction "1_1") (pintype "passive"))
      (node (ref "R126") (pin "1") (pinfunction "1_1") (pintype "passive"))
      (node (ref "R128") (pin "1") (pinfunction "1_1") (pintype "passive"))
      (node (ref "R130") (pin "1") (pinfunction "1_1") (pintype "passive"))
      (node (ref "R132") (pin "1") (pinfunction "1_1") (pintype "passive"))
      (node (ref "R134") (pin "1") (pinfunction "1_1") (pintype "passive"))
      (node (ref "R72") (pin "1") (pinfunction "1_1") (pintype "passive"))
      (node (ref "R74") (pin "1") (pinfunction "1_1") (pintype "passive"))
      (node (ref "R76") (pin "1") (pinfunction "1_1") (pintype "passive"))
      (node (ref "R78") (pin "1") (pinfunction "1_1") (pintype "passive"))
      (node (ref "R80") (pin "1") (pinfunction "1_1") (pintype "passive"))
      (node (ref "R82") (pin "1") (pinfunction "1_1") (pintype "passive"))
      (node (ref "R84") (pin "1") (pinfunction "1_1") (pintype "passive"))
      (node (ref "R86") (pin "1") (pinfunction "1_1") (pintype "passive"))
      (node (ref "R88") (pin "1") (pinfunction "1_1") (pintype "passive"))
      (node (ref "R90") (pin "1") (pinfunction "1_1") (pintype "passive"))
      (node (ref "R92") (pin "1") (pinfunction "1_1") (pintype "passive"))
      (node (ref "R94") (pin "1") (pinfunction "1_1") (pintype "passive"))
      (node (ref "R96") (pin "1") (pinfunction "1_1") (pintype "passive"))
      (node (ref "R98") (pin "1") (pinfunction "1_1") (pintype "passive"))
      (node (ref "R99") (pin "1") (pinfunction "1_1") (pintype "passive"))
      (node (ref "U26") (pin "16") (pinfunction "VCC_16") (pintype "passive"))
      (node (ref "U27") (pin "16") (pinfunction "VCC_16") (pintype "passive"))
      (node (ref "U30") (pin "16") (pinfunction "VCC_16") (pintype "passive"))
      (node (ref "U31") (pin "16") (pinfunction "VCC_16") (pintype "passive"))
    )
    (net (code "105") (name "unconnected-(P7-Pad9)") (class "Default")
      (node (ref "P7") (pin "9") (pinfunction "9_9") (pintype "passive"))
    )
    (net (code "106") (name "unconnected-(P12-Pad9)") (class "Default")
      (node (ref "P12") (pin "9") (pinfunction "9_9") (pintype "passive"))
    )
    (net (code "107") (name "unconnected-(P14-Pad9)") (class "Default")
      (node (ref "P14") (pin "9") (pinfunction "9_9") (pintype "passive"))
    )
    (net (code "108") (name "unconnected-(U26-Q7#-Pad7)") (class "Default")
      (node (ref "U26") (pin "7") (pinfunction "Q7#_7") (pintype "passive"))
    )
    (net (code "109") (name "unconnected-(U26-Q7-Pad9)") (class "Default")
      (node (ref "U26") (pin "9") (pinfunction "Q7_9") (pintype "passive"))
    )
    (net (code "110") (name "unconnected-(U27-Q7#-Pad7)") (class "Default")
      (node (ref "U27") (pin "7") (pinfunction "Q7#_7") (pintype "passive"))
    )
    (net (code "111") (name "unconnected-(U30-DS-Pad10)") (class "Default")
      (node (ref "U30") (pin "10") (pinfunction "DS_10") (pintype "passive"))
    )
    (net (code "112") (name "unconnected-(U30-Q7#-Pad7)") (class "Default")
      (node (ref "U30") (pin "7") (pinfunction "Q7#_7") (pintype "passive"))
    )
    (net (code "113") (name "unconnected-(U31-Q7#-Pad7)") (class "Default")
      (node (ref "U31") (pin "7") (pinfunction "Q7#_7") (pintype "passive"))
    )
  )
)
